# TapTempo.net
KiCad netlist of a schematic drawn in EAGLE
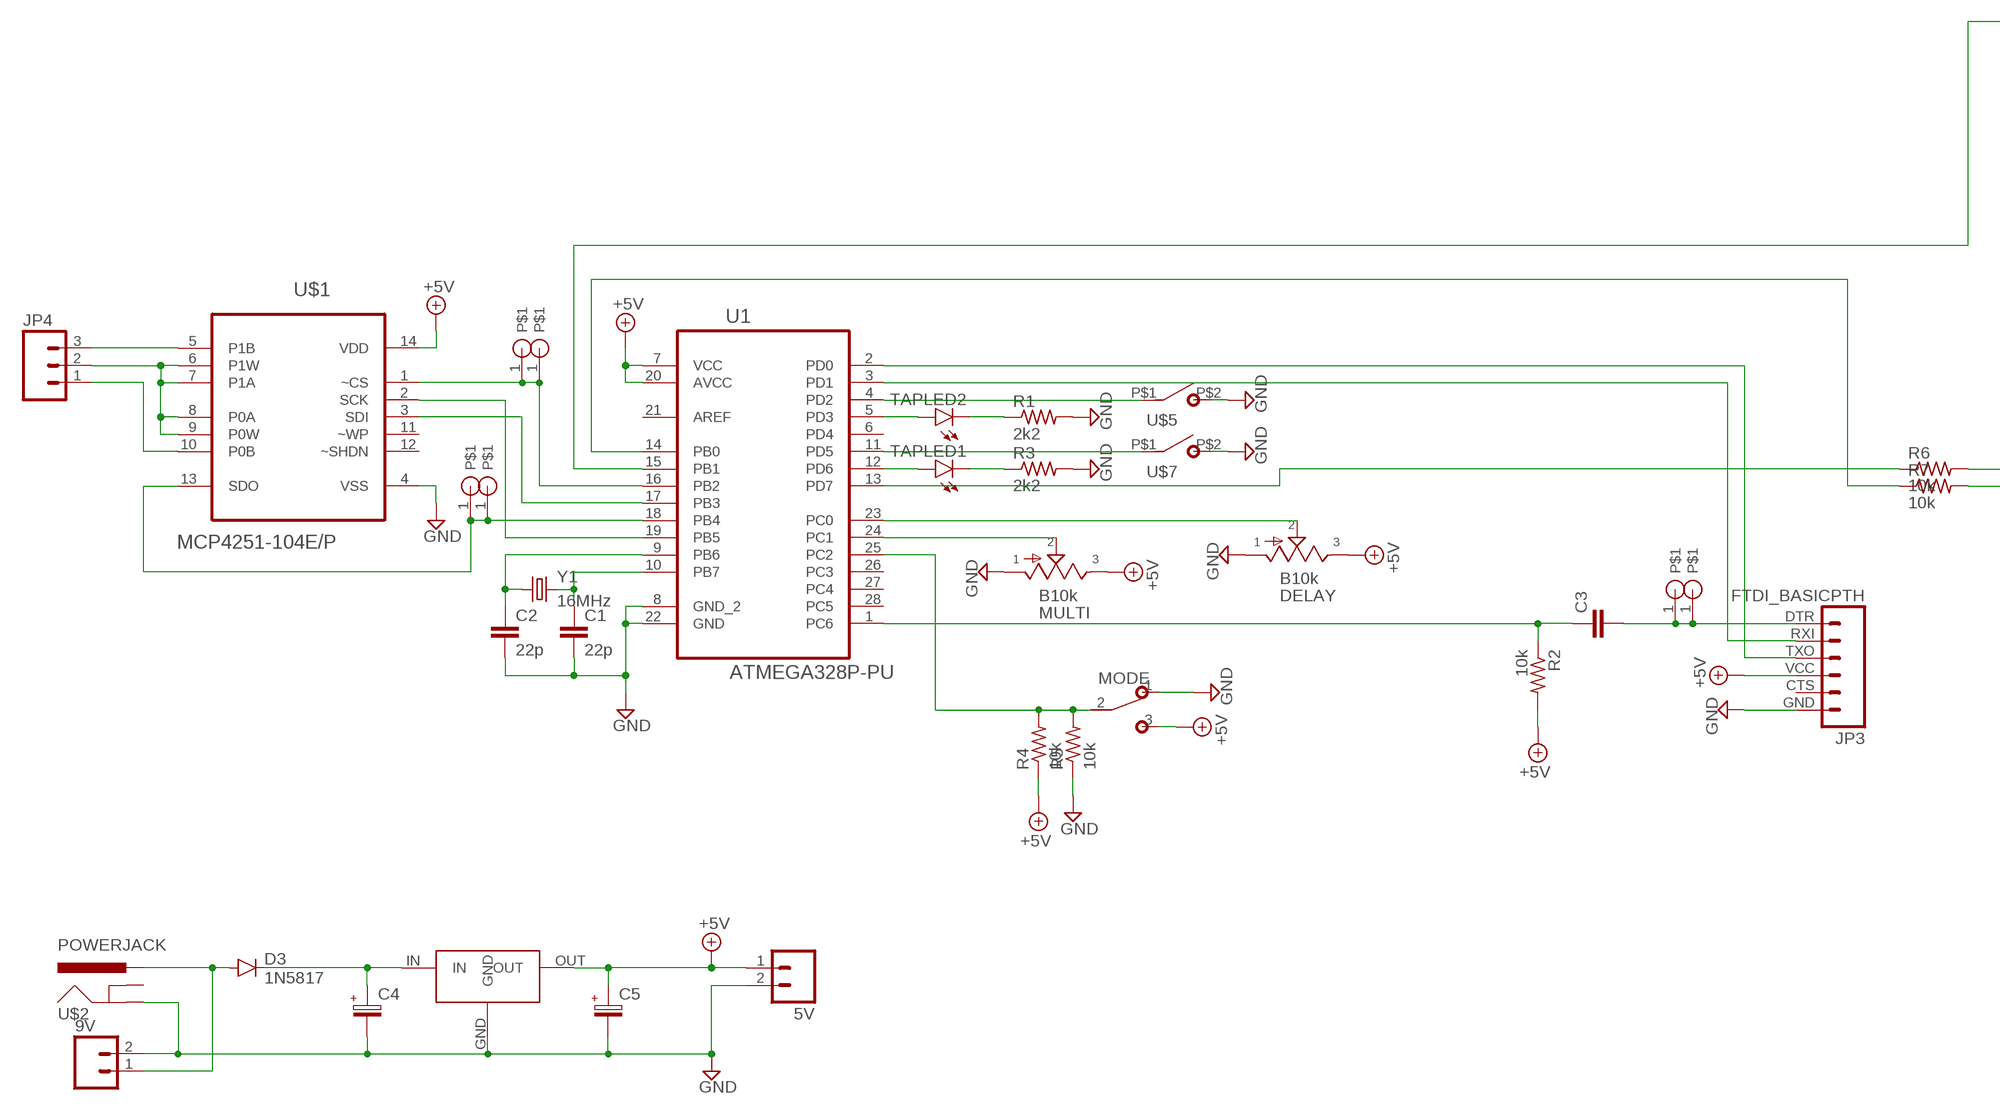
[diagram p0: schematic, sheet 1, part 1 of 2]
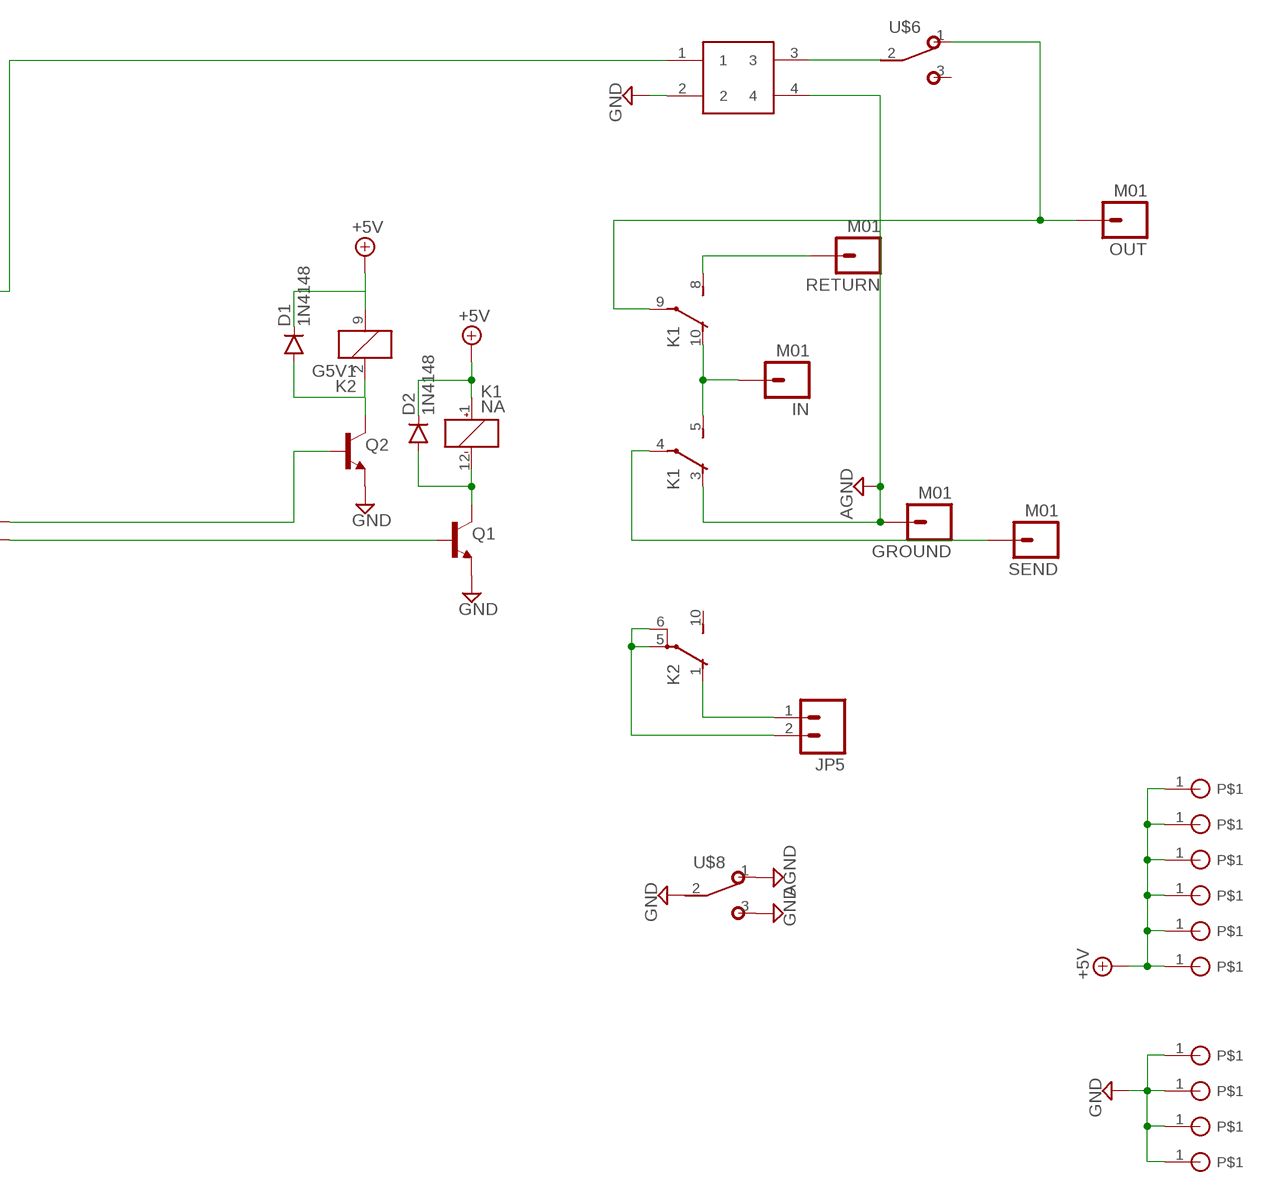
[diagram p1: schematic, sheet 1, part 2 of 2]

(export (version "E")
  (design (tool "Eeschema 10.0.6"))
  (components
    (comp (ref "5V")
      (value "M02PTH")
      (footprint "eagle-import:1X02")
      (libsource (lib "eagle-import") (part "M02PTH"))
    )
    (comp (ref "9V")
      (value "M02PTH")
      (footprint "eagle-import:1X02")
      (libsource (lib "eagle-import") (part "M02PTH"))
    )
    (comp (ref "C1")
      (value "22p")
      (footprint "eagle-import:PITCH_2,5")
      (libsource (lib "eagle-import") (part "CAPACITORCERAMIC2,5"))
    )
    (comp (ref "C2")
      (value "22p")
      (footprint "eagle-import:PITCH_2,5")
      (libsource (lib "eagle-import") (part "CAPACITORCERAMIC2,5"))
    )
    (comp (ref "C3")
      (value "CAPACITORW2.5")
      (footprint "eagle-import:W2.5")
      (libsource (lib "eagle-import") (part "CAPACITORW2.5"))
    )
    (comp (ref "C4")
      (value "CAP_POLD6,3")
      (footprint "eagle-import:POL_D6,3")
      (libsource (lib "eagle-import") (part "CAP_POLD6,3"))
    )
    (comp (ref "C5")
      (value "CAP_POLD6,3")
      (footprint "eagle-import:POL_D6,3")
      (libsource (lib "eagle-import") (part "CAP_POLD6,3"))
    )
    (comp (ref "D1")
      (value "1N4148")
      (footprint "eagle-import:DIODE-1N4148")
      (libsource (lib "eagle-import") (part "DIODE1N4148"))
    )
    (comp (ref "D2")
      (value "1N4148")
      (footprint "eagle-import:DIODE-1N4148")
      (libsource (lib "eagle-import") (part "DIODE1N4148"))
    )
    (comp (ref "D3")
      (value "1N5817")
      (footprint "eagle-import:DIODE-1N4001")
      (libsource (lib "eagle-import") (part "DIODEPTH"))
    )
    (comp (ref "DELAY")
      (value "B10k")
      (footprint "eagle-import:16MM")
      (libsource (lib "eagle-import") (part "POT_ANGLED"))
    )
    (comp (ref "GROUND")
      (value "M01")
      (footprint "eagle-import:1X01")
      (libsource (lib "eagle-import") (part "M01"))
    )
    (comp (ref "IN")
      (value "M01")
      (footprint "eagle-import:1X01")
      (libsource (lib "eagle-import") (part "M01"))
    )
    (comp (ref "JP3")
      (value "FTDI_BASICPTH")
      (footprint "eagle-import:FTDI_BASIC")
      (libsource (lib "eagle-import") (part "FTDI_BASICPTH"))
    )
    (comp (ref "JP4")
      (value "M03PTH")
      (footprint "eagle-import:1X03")
      (libsource (lib "eagle-import") (part "M03PTH"))
    )
    (comp (ref "JP5")
      (value "M02PTH")
      (footprint "eagle-import:1X02")
      (libsource (lib "eagle-import") (part "M02PTH"))
    )
    (comp (ref "K1") (value "NA") (footprint "eagle-import:NA") (libsource (lib "eagle-import") (part "NA")))
    (comp (ref "K2")
      (value "G5V1")
      (footprint "eagle-import:G5V1")
      (fields (field (name "MPN") "G5V-1-DC24"))
      (libsource (lib "eagle-import") (part "G5V1"))
    )
    (comp (ref "L1")
      (value "M01_LINK")
      (footprint "eagle-import:1X01")
      (libsource (lib "eagle-import") (part "M01_LINK"))
    )
    (comp (ref "L2")
      (value "M01_LINK")
      (footprint "eagle-import:1X01")
      (libsource (lib "eagle-import") (part "M01_LINK"))
    )
    (comp (ref "L3")
      (value "M01_LINK")
      (footprint "eagle-import:1X01")
      (libsource (lib "eagle-import") (part "M01_LINK"))
    )
    (comp (ref "L4")
      (value "M01_LINK")
      (footprint "eagle-import:1X01")
      (libsource (lib "eagle-import") (part "M01_LINK"))
    )
    (comp (ref "L5")
      (value "M01_LINK")
      (footprint "eagle-import:1X01")
      (libsource (lib "eagle-import") (part "M01_LINK"))
    )
    (comp (ref "L6")
      (value "M01_LINK")
      (footprint "eagle-import:1X01")
      (libsource (lib "eagle-import") (part "M01_LINK"))
    )
    (comp (ref "L7")
      (value "M01_LINK")
      (footprint "eagle-import:1X01")
      (libsource (lib "eagle-import") (part "M01_LINK"))
    )
    (comp (ref "L8")
      (value "M01_LINK")
      (footprint "eagle-import:1X01")
      (libsource (lib "eagle-import") (part "M01_LINK"))
    )
    (comp (ref "L9")
      (value "M01_LINK")
      (footprint "eagle-import:1X01")
      (libsource (lib "eagle-import") (part "M01_LINK"))
    )
    (comp (ref "L10")
      (value "M01_LINK")
      (footprint "eagle-import:1X01")
      (libsource (lib "eagle-import") (part "M01_LINK"))
    )
    (comp (ref "L11")
      (value "M01_LINK")
      (footprint "eagle-import:1X01")
      (libsource (lib "eagle-import") (part "M01_LINK"))
    )
    (comp (ref "L12")
      (value "M01_LINK")
      (footprint "eagle-import:1X01")
      (libsource (lib "eagle-import") (part "M01_LINK"))
    )
    (comp (ref "L13")
      (value "M01_LINK")
      (footprint "eagle-import:1X01")
      (libsource (lib "eagle-import") (part "M01_LINK"))
    )
    (comp (ref "L14")
      (value "M01_LINK")
      (footprint "eagle-import:1X01")
      (libsource (lib "eagle-import") (part "M01_LINK"))
    )
    (comp (ref "L15")
      (value "M01_LINK")
      (footprint "eagle-import:1X01")
      (libsource (lib "eagle-import") (part "M01_LINK"))
    )
    (comp (ref "L16")
      (value "M01_LINK")
      (footprint "eagle-import:1X01")
      (libsource (lib "eagle-import") (part "M01_LINK"))
    )
    (comp (ref "MODE")
      (value "TOGGLE-SPDT")
      (footprint "eagle-import:TOGGLE-SPDT")
      (libsource (lib "eagle-import") (part "TOGGLE-SPDT"))
    )
    (comp (ref "MULTI")
      (value "B10k")
      (footprint "eagle-import:16MM")
      (libsource (lib "eagle-import") (part "POT_ANGLED"))
    )
    (comp (ref "OUT")
      (value "M01")
      (footprint "eagle-import:1X01")
      (libsource (lib "eagle-import") (part "M01"))
    )
    (comp (ref "Q1")
      (value "NPN")
      (footprint "eagle-import:TO92")
      (libsource (lib "eagle-import") (part "NPN"))
    )
    (comp (ref "Q2")
      (value "NPN")
      (footprint "eagle-import:TO92")
      (libsource (lib "eagle-import") (part "NPN"))
    )
    (comp (ref "R1")
      (value "2k2")
      (footprint "eagle-import:R0207_3")
      (libsource (lib "eagle-import") (part "RESISTORPITCH_3"))
    )
    (comp (ref "R2")
      (value "10k")
      (footprint "eagle-import:R0207_3")
      (libsource (lib "eagle-import") (part "RESISTORPITCH_3"))
    )
    (comp (ref "R3")
      (value "2k2")
      (footprint "eagle-import:R0207_3")
      (libsource (lib "eagle-import") (part "RESISTORPITCH_3"))
    )
    (comp (ref "R4")
      (value "10k")
      (footprint "eagle-import:R0207_3")
      (libsource (lib "eagle-import") (part "RESISTORPITCH_3"))
    )
    (comp (ref "R5")
      (value "10k")
      (footprint "eagle-import:R0207_3")
      (libsource (lib "eagle-import") (part "RESISTORPITCH_3"))
    )
    (comp (ref "R6")
      (value "10k")
      (footprint "eagle-import:R0207_3")
      (libsource (lib "eagle-import") (part "RESISTORPITCH_3"))
    )
    (comp (ref "R7")
      (value "10k")
      (footprint "eagle-import:R0207_3")
      (libsource (lib "eagle-import") (part "RESISTORPITCH_3"))
    )
    (comp (ref "RETURN")
      (value "M01")
      (footprint "eagle-import:1X01")
      (libsource (lib "eagle-import") (part "M01"))
    )
    (comp (ref "SEND")
      (value "M01")
      (footprint "eagle-import:1X01")
      (libsource (lib "eagle-import") (part "M01"))
    )
    (comp (ref "TAPLED1")
      (value "LED5MM")
      (footprint "eagle-import:LED5MM")
      (libsource (lib "eagle-import") (part "LED5MM"))
    )
    (comp (ref "TAPLED2")
      (value "LED5MM")
      (footprint "eagle-import:LED5MM")
      (libsource (lib "eagle-import") (part "LED5MM"))
    )
    (comp (ref "U$1")
      (value "MCP4251-104E/P")
      (footprint "eagle-import:DIP254P762X533-14")
      (libsource (lib "eagle-import") (part "MCP4251-104E/P"))
    )
    (comp (ref "U$2")
      (value "POWERJACK")
      (footprint "eagle-import:POWER2.1")
      (libsource (lib "eagle-import") (part "POWERJACK"))
    )
    (comp (ref "U$3")
      (value "78LXX")
      (footprint "eagle-import:TO92")
      (libsource (lib "eagle-import") (part "78LXX"))
    )
    (comp (ref "U$4")
      (value "TLP222A")
      (footprint "eagle-import:TLP222A")
      (libsource (lib "eagle-import") (part "TLP222A"))
    )
    (comp (ref "U$5")
      (value "FOOT-SPST_SOFT")
      (footprint "eagle-import:FOOT-SPST_SOFT")
      (libsource (lib "eagle-import") (part "FOOT-SPST_SOFT"))
    )
    (comp (ref "U$6")
      (value "TOGGLE-SPDTSUB")
      (footprint "eagle-import:SPDT_SUB")
      (libsource (lib "eagle-import") (part "TOGGLE-SPDTSUB"))
    )
    (comp (ref "U$7")
      (value "FOOT-SPST_SOFT")
      (footprint "eagle-import:FOOT-SPST_SOFT")
      (libsource (lib "eagle-import") (part "FOOT-SPST_SOFT"))
    )
    (comp (ref "U$8")
      (value "TOGGLE-SPDTSUB")
      (footprint "eagle-import:SPDT_SUB")
      (libsource (lib "eagle-import") (part "TOGGLE-SPDTSUB"))
    )
    (comp (ref "U1")
      (value "ATMEGA328P-PU")
      (footprint "eagle-import:DIP254P762X457-28")
      (libsource (lib "eagle-import") (part "ATMEGA328P-PU"))
    )
    (comp (ref "Y1")
      (value "16MHz")
      (footprint "eagle-import:HC49US")
      (libsource (lib "eagle-import") (part "CRYSTALHC49US"))
    )
  )
  (nets
    (net (code "1") (name "+5V") (class "Default")
      (node (ref "5V") (pin "1") (pinfunction "1_1") (pintype "passive"))
      (node (ref "C5") (pin "+") (pinfunction "+_+") (pintype "passive"))
      (node (ref "D1") (pin "C") (pinfunction "C_C") (pintype "passive"))
      (node (ref "D2") (pin "C") (pinfunction "C_C") (pintype "passive"))
      (node (ref "DELAY") (pin "3") (pinfunction "3_3") (pintype "passive"))
      (node (ref "JP3") (pin "VCC") (pinfunction "4_VCC") (pintype "passive"))
      (node (ref "K1") (pin "1") (pinfunction "+_1") (pintype "passive"))
      (node (ref "K2") (pin "9") (pinfunction "2_9") (pintype "passive"))
      (node (ref "L1") (pin "1") (pinfunction "P$1_1") (pintype "bidirectional"))
      (node (ref "L13") (pin "1") (pinfunction "P$1_1") (pintype "bidirectional"))
      (node (ref "L14") (pin "1") (pinfunction "P$1_1") (pintype "bidirectional"))
      (node (ref "L15") (pin "1") (pinfunction "P$1_1") (pintype "bidirectional"))
      (node (ref "L16") (pin "1") (pinfunction "P$1_1") (pintype "bidirectional"))
      (node (ref "L2") (pin "1") (pinfunction "P$1_1") (pintype "bidirectional"))
      (node (ref "MODE") (pin "3") (pinfunction "3_3") (pintype "passive"))
      (node (ref "MULTI") (pin "3") (pinfunction "3_3") (pintype "passive"))
      (node (ref "R2") (pin "2") (pinfunction "2_2") (pintype "passive"))
      (node (ref "R4") (pin "1") (pinfunction "1_1") (pintype "passive"))
      (node (ref "U$1") (pin "14") (pinfunction "VDD_14") (pintype "power_in"))
      (node (ref "U$3") (pin "OUT") (pinfunction "OUT_OUT") (pintype "bidirectional"))
      (node (ref "U1") (pin "20") (pinfunction "AVCC_20") (pintype "power_in"))
      (node (ref "U1") (pin "7") (pinfunction "VCC_7") (pintype "power_in"))
    )
    (net (code "2") (name "AGND") (class "Default")
      (node (ref "GROUND") (pin "1") (pinfunction "1_1") (pintype "passive"))
      (node (ref "K1") (pin "3") (pinfunction "O_3") (pintype "passive"))
      (node (ref "U$4") (pin "4") (pinfunction "4_4") (pintype "bidirectional"))
      (node (ref "U$8") (pin "1") (pinfunction "1_1") (pintype "passive"))
    )
    (net (code "3") (name "GND") (class "Default")
      (node (ref "5V") (pin "2") (pinfunction "2_2") (pintype "passive"))
      (node (ref "9V") (pin "2") (pinfunction "2_2") (pintype "passive"))
      (node (ref "C1") (pin "P$2") (pinfunction "2_P$2") (pintype "passive"))
      (node (ref "C2") (pin "P$2") (pinfunction "2_P$2") (pintype "passive"))
      (node (ref "C4") (pin "-") (pinfunction "-_-") (pintype "passive"))
      (node (ref "C5") (pin "-") (pinfunction "-_-") (pintype "passive"))
      (node (ref "DELAY") (pin "1") (pinfunction "1_1") (pintype "passive"))
      (node (ref "JP3") (pin "GND") (pinfunction "6_GND") (pintype "passive"))
      (node (ref "L11") (pin "1") (pinfunction "P$1_1") (pintype "bidirectional"))
      (node (ref "L12") (pin "1") (pinfunction "P$1_1") (pintype "bidirectional"))
      (node (ref "L3") (pin "1") (pinfunction "P$1_1") (pintype "bidirectional"))
      (node (ref "L4") (pin "1") (pinfunction "P$1_1") (pintype "bidirectional"))
      (node (ref "MODE") (pin "1") (pinfunction "1_1") (pintype "passive"))
      (node (ref "MULTI") (pin "1") (pinfunction "1_1") (pintype "passive"))
      (node (ref "Q1") (pin "E") (pinfunction "E_E") (pintype "passive"))
      (node (ref "Q2") (pin "E") (pinfunction "E_E") (pintype "passive"))
      (node (ref "R1") (pin "2") (pinfunction "2_2") (pintype "passive"))
      (node (ref "R3") (pin "2") (pinfunction "2_2") (pintype "passive"))
      (node (ref "R5") (pin "1") (pinfunction "1_1") (pintype "passive"))
      (node (ref "U$1") (pin "4") (pinfunction "VSS_4") (pintype "power_in"))
      (node (ref "U$2") (pin "GND") (pinfunction "GND_GND") (pintype "bidirectional"))
      (node (ref "U$3") (pin "GND") (pinfunction "GND_GND") (pintype "bidirectional"))
      (node (ref "U$4") (pin "2") (pinfunction "2_2") (pintype "bidirectional"))
      (node (ref "U$5") (pin "P$2") (pinfunction "S_P$2") (pintype "passive"))
      (node (ref "U$7") (pin "P$2") (pinfunction "S_P$2") (pintype "passive"))
      (node (ref "U$8") (pin "2") (pinfunction "2_2") (pintype "passive"))
      (node (ref "U$8") (pin "3") (pinfunction "3_3") (pintype "passive"))
      (node (ref "U1") (pin "22") (pinfunction "GND_22") (pintype "passive"))
      (node (ref "U1") (pin "8") (pinfunction "GND_2_8") (pintype "passive"))
    )
    (net (code "4") (name "Net-(C1-1)") (class "Default")
      (node (ref "C1") (pin "P$1") (pinfunction "1_P$1") (pintype "passive"))
      (node (ref "U1") (pin "10") (pinfunction "PB7_10") (pintype "bidirectional"))
      (node (ref "Y1") (pin "2") (pinfunction "2_2") (pintype "passive"))
    )
    (net (code "5") (name "Net-(C2-1)") (class "Default")
      (node (ref "C2") (pin "P$1") (pinfunction "1_P$1") (pintype "passive"))
      (node (ref "U1") (pin "9") (pinfunction "PB6_9") (pintype "bidirectional"))
      (node (ref "Y1") (pin "1") (pinfunction "1_1") (pintype "passive"))
    )
    (net (code "6") (name "Net-(C4-Pad+)") (class "Default")
      (node (ref "C4") (pin "+") (pinfunction "+_+") (pintype "passive"))
      (node (ref "D3") (pin "C") (pinfunction "C_C") (pintype "passive"))
      (node (ref "U$3") (pin "IN") (pinfunction "IN_IN") (pintype "bidirectional"))
    )
    (net (code "7") (name "Net-(JP3-1)") (class "Default")
      (node (ref "C3") (pin "2") (pinfunction "2_2") (pintype "passive"))
      (node (ref "JP3") (pin "DTR") (pinfunction "1_DTR") (pintype "passive"))
      (node (ref "L10") (pin "1") (pinfunction "P$1_1") (pintype "bidirectional"))
      (node (ref "L9") (pin "1") (pinfunction "P$1_1") (pintype "bidirectional"))
    )
    (net (code "8") (name "Net-(JP3-2)") (class "Default")
      (node (ref "JP3") (pin "RXI") (pinfunction "2_RXI") (pintype "passive"))
      (node (ref "U1") (pin "3") (pinfunction "PD1_3") (pintype "bidirectional"))
    )
    (net (code "9") (name "Net-(JP3-3)") (class "Default")
      (node (ref "JP3") (pin "TXO") (pinfunction "3_TXO") (pintype "passive"))
      (node (ref "U1") (pin "2") (pinfunction "PD0_2") (pintype "bidirectional"))
    )
    (net (code "10") (name "Net-(JP5-Pad2)") (class "Default")
      (node (ref "JP5") (pin "2") (pinfunction "2_2") (pintype "passive"))
      (node (ref "K2") (pin "5") (pinfunction "P_5") (pintype "passive"))
      (node (ref "K2") (pin "6") (pinfunction "P_6") (pintype "passive"))
    )
    (net (code "11") (name "Net-(K1A--)") (class "Default")
      (node (ref "D2") (pin "A") (pinfunction "A_A") (pintype "passive"))
      (node (ref "K1") (pin "12") (pinfunction "-_12") (pintype "passive"))
      (node (ref "Q1") (pin "C") (pinfunction "C_C") (pintype "passive"))
    )
    (net (code "12") (name "Net-(K1B-P)") (class "Default")
      (node (ref "K1") (pin "4") (pinfunction "P_4") (pintype "passive"))
      (node (ref "SEND") (pin "1") (pinfunction "1_1") (pintype "passive"))
    )
    (net (code "13") (name "Net-(K1B-S)") (class "Default")
      (node (ref "IN") (pin "1") (pinfunction "1_1") (pintype "passive"))
      (node (ref "K1") (pin "10") (pinfunction "O_10") (pintype "passive"))
      (node (ref "K1") (pin "5") (pinfunction "S_5") (pintype "passive"))
    )
    (net (code "14") (name "Net-(K1C-P)") (class "Default")
      (node (ref "K1") (pin "9") (pinfunction "P_9") (pintype "passive"))
      (node (ref "OUT") (pin "1") (pinfunction "1_1") (pintype "passive"))
      (node (ref "U$6") (pin "1") (pinfunction "1_1") (pintype "passive"))
    )
    (net (code "15") (name "Net-(K1C-S)") (class "Default")
      (node (ref "K1") (pin "8") (pinfunction "S_8") (pintype "passive"))
      (node (ref "RETURN") (pin "1") (pinfunction "1_1") (pintype "passive"))
    )
    (net (code "16") (name "Net-(K2A-1)") (class "Default")
      (node (ref "D1") (pin "A") (pinfunction "A_A") (pintype "passive"))
      (node (ref "K2") (pin "2") (pinfunction "1_2") (pintype "passive"))
      (node (ref "Q2") (pin "C") (pinfunction "C_C") (pintype "passive"))
    )
    (net (code "17") (name "Net-(K2B-O)") (class "Default")
      (node (ref "JP5") (pin "1") (pinfunction "1_1") (pintype "passive"))
      (node (ref "K2") (pin "1") (pinfunction "O_1") (pintype "passive"))
    )
    (net (code "18") (name "Net-(L5-P$1)") (class "Default")
      (node (ref "L5") (pin "1") (pinfunction "P$1_1") (pintype "bidirectional"))
      (node (ref "L6") (pin "1") (pinfunction "P$1_1") (pintype "bidirectional"))
      (node (ref "U$1") (pin "13") (pinfunction "SDO_13") (pintype "output"))
      (node (ref "U1") (pin "18") (pinfunction "PB4_18") (pintype "bidirectional"))
    )
    (net (code "19") (name "Net-(L7-P$1)") (class "Default")
      (node (ref "L7") (pin "1") (pinfunction "P$1_1") (pintype "bidirectional"))
      (node (ref "L8") (pin "1") (pinfunction "P$1_1") (pintype "bidirectional"))
      (node (ref "U$1") (pin "1") (pinfunction "~{CS}_1") (pintype "input"))
      (node (ref "U1") (pin "16") (pinfunction "PB2_16") (pintype "bidirectional"))
    )
    (net (code "20") (name "Net-(Q1-PadB)") (class "Default")
      (node (ref "Q1") (pin "B") (pinfunction "B_B") (pintype "passive"))
      (node (ref "R7") (pin "2") (pinfunction "2_2") (pintype "passive"))
    )
    (net (code "21") (name "Net-(Q2-PadB)") (class "Default")
      (node (ref "Q2") (pin "B") (pinfunction "B_B") (pintype "passive"))
      (node (ref "R6") (pin "2") (pinfunction "2_2") (pintype "passive"))
    )
    (net (code "22") (name "Net-(R1-Pad1)") (class "Default")
      (node (ref "R1") (pin "1") (pinfunction "1_1") (pintype "passive"))
      (node (ref "TAPLED2") (pin "C") (pinfunction "C_C") (pintype "passive"))
    )
    (net (code "23") (name "Net-(R3-Pad1)") (class "Default")
      (node (ref "R3") (pin "1") (pinfunction "1_1") (pintype "passive"))
      (node (ref "TAPLED1") (pin "C") (pinfunction "C_C") (pintype "passive"))
    )
    (net (code "24") (name "Net-(U$1-P0A)") (class "Default")
      (node (ref "JP4") (pin "2") (pinfunction "2_2") (pintype "passive"))
      (node (ref "U$1") (pin "6") (pinfunction "P1W_6") (pintype "passive"))
      (node (ref "U$1") (pin "7") (pinfunction "P1A_7") (pintype "passive"))
      (node (ref "U$1") (pin "8") (pinfunction "P0A_8") (pintype "passive"))
      (node (ref "U$1") (pin "9") (pinfunction "P0W_9") (pintype "passive"))
    )
    (net (code "25") (name "Net-(U$1-P0B)") (class "Default")
      (node (ref "JP4") (pin "1") (pinfunction "1_1") (pintype "passive"))
      (node (ref "U$1") (pin "10") (pinfunction "P0B_10") (pintype "passive"))
    )
    (net (code "26") (name "Net-(U$1-P1B)") (class "Default")
      (node (ref "JP4") (pin "3") (pinfunction "3_3") (pintype "passive"))
      (node (ref "U$1") (pin "5") (pinfunction "P1B_5") (pintype "passive"))
    )
    (net (code "27") (name "Net-(U$1-SCK)") (class "Default")
      (node (ref "U$1") (pin "2") (pinfunction "SCK_2") (pintype "input"))
      (node (ref "U1") (pin "19") (pinfunction "PB5_19") (pintype "bidirectional"))
    )
    (net (code "28") (name "Net-(U$1-SDI)") (class "Default")
      (node (ref "U$1") (pin "3") (pinfunction "SDI_3") (pintype "input"))
      (node (ref "U1") (pin "17") (pinfunction "PB3_17") (pintype "bidirectional"))
    )
    (net (code "29") (name "Net-(U$2-PWR)") (class "Default")
      (node (ref "9V") (pin "1") (pinfunction "1_1") (pintype "passive"))
      (node (ref "D3") (pin "A") (pinfunction "A_A") (pintype "passive"))
      (node (ref "U$2") (pin "VCC") (pinfunction "PWR_VCC") (pintype "bidirectional"))
    )
    (net (code "30") (name "Net-(U$4-Pad3)") (class "Default")
      (node (ref "U$4") (pin "3") (pinfunction "3_3") (pintype "bidirectional"))
      (node (ref "U$6") (pin "2") (pinfunction "2_2") (pintype "passive"))
    )
    (net (code "31") (name "Net-(U$5-P)") (class "Default")
      (node (ref "U$5") (pin "P$1") (pinfunction "P_P$1") (pintype "passive"))
      (node (ref "U1") (pin "4") (pinfunction "PD2_4") (pintype "bidirectional"))
    )
    (net (code "32") (name "Net-(U$7-P)") (class "Default")
      (node (ref "U$7") (pin "P$1") (pinfunction "P_P$1") (pintype "passive"))
      (node (ref "U1") (pin "11") (pinfunction "PD5_11") (pintype "bidirectional"))
    )
    (net (code "33") (name "Net-(U1-PB0)") (class "Default")
      (node (ref "R7") (pin "1") (pinfunction "1_1") (pintype "passive"))
      (node (ref "U1") (pin "14") (pinfunction "PB0_14") (pintype "bidirectional"))
    )
    (net (code "34") (name "Net-(U1-PB1)") (class "Default")
      (node (ref "U$4") (pin "1") (pinfunction "1_1") (pintype "bidirectional"))
      (node (ref "U1") (pin "15") (pinfunction "PB1_15") (pintype "bidirectional"))
    )
    (net (code "35") (name "Net-(U1-PC0)") (class "Default")
      (node (ref "DELAY") (pin "2") (pinfunction "2_2") (pintype "passive"))
      (node (ref "U1") (pin "23") (pinfunction "PC0_23") (pintype "bidirectional"))
    )
    (net (code "36") (name "Net-(U1-PC1)") (class "Default")
      (node (ref "MULTI") (pin "2") (pinfunction "2_2") (pintype "passive"))
      (node (ref "U1") (pin "24") (pinfunction "PC1_24") (pintype "bidirectional"))
    )
    (net (code "37") (name "Net-(U1-PC2)") (class "Default")
      (node (ref "MODE") (pin "2") (pinfunction "2_2") (pintype "passive"))
      (node (ref "R4") (pin "2") (pinfunction "2_2") (pintype "passive"))
      (node (ref "R5") (pin "2") (pinfunction "2_2") (pintype "passive"))
      (node (ref "U1") (pin "25") (pinfunction "PC2_25") (pintype "bidirectional"))
    )
    (net (code "38") (name "Net-(U1-PC6)") (class "Default")
      (node (ref "C3") (pin "1") (pinfunction "1_1") (pintype "passive"))
      (node (ref "R2") (pin "1") (pinfunction "1_1") (pintype "passive"))
      (node (ref "U1") (pin "1") (pinfunction "PC6_1") (pintype "bidirectional"))
    )
    (net (code "39") (name "Net-(U1-PD3)") (class "Default")
      (node (ref "TAPLED2") (pin "A") (pinfunction "A_A") (pintype "passive"))
      (node (ref "U1") (pin "5") (pinfunction "PD3_5") (pintype "bidirectional"))
    )
    (net (code "40") (name "Net-(U1-PD6)") (class "Default")
      (node (ref "TAPLED1") (pin "A") (pinfunction "A_A") (pintype "passive"))
      (node (ref "U1") (pin "12") (pinfunction "PD6_12") (pintype "bidirectional"))
    )
    (net (code "41") (name "Net-(U1-PD7)") (class "Default")
      (node (ref "R6") (pin "1") (pinfunction "1_1") (pintype "passive"))
      (node (ref "U1") (pin "13") (pinfunction "PD7_13") (pintype "bidirectional"))
    )
    (net (code "42") (name "unconnected-(JP3-5-PadCTS)") (class "Default")
      (node (ref "JP3") (pin "CTS") (pinfunction "5_CTS") (pintype "passive"))
    )
    (net (code "43") (name "unconnected-(K2B-S-Pad10)") (class "Default")
      (node (ref "K2") (pin "10") (pinfunction "S_10") (pintype "passive"))
    )
    (net (code "44") (name "unconnected-(U$1-~{SHDN}-Pad12)") (class "Default")
      (node (ref "U$1") (pin "12") (pinfunction "~{SHDN}_12") (pintype "input"))
    )
    (net (code "45") (name "unconnected-(U$1-~{WP}-Pad11)") (class "Default")
      (node (ref "U$1") (pin "11") (pinfunction "~{WP}_11") (pintype "input"))
    )
    (net (code "46") (name "unconnected-(U$2-GNDBREAK-PadGND_BRK)") (class "Default")
      (node (ref "U$2") (pin "GND_BRK") (pinfunction "GNDBREAK_GND_BRK") (pintype "bidirectional"))
    )
    (net (code "47") (name "unconnected-(U$6-Pad3)") (class "Default")
      (node (ref "U$6") (pin "3") (pinfunction "3_3") (pintype "passive"))
    )
    (net (code "48") (name "unconnected-(U1-AREF-Pad21)") (class "Default")
      (node (ref "U1") (pin "21") (pinfunction "AREF_21") (pintype "input"))
    )
    (net (code "49") (name "unconnected-(U1-PC3-Pad26)") (class "Default")
      (node (ref "U1") (pin "26") (pinfunction "PC3_26") (pintype "bidirectional"))
    )
    (net (code "50") (name "unconnected-(U1-PC4-Pad27)") (class "Default")
      (node (ref "U1") (pin "27") (pinfunction "PC4_27") (pintype "bidirectional"))
    )
    (net (code "51") (name "unconnected-(U1-PC5-Pad28)") (class "Default")
      (node (ref "U1") (pin "28") (pinfunction "PC5_28") (pintype "bidirectional"))
    )
    (net (code "52") (name "unconnected-(U1-PD4-Pad6)") (class "Default")
      (node (ref "U1") (pin "6") (pinfunction "PD4_6") (pintype "bidirectional"))
    )
  )
)
